# NEW_PDB.net
KiCad netlist of a schematic drawn in Altium Designer
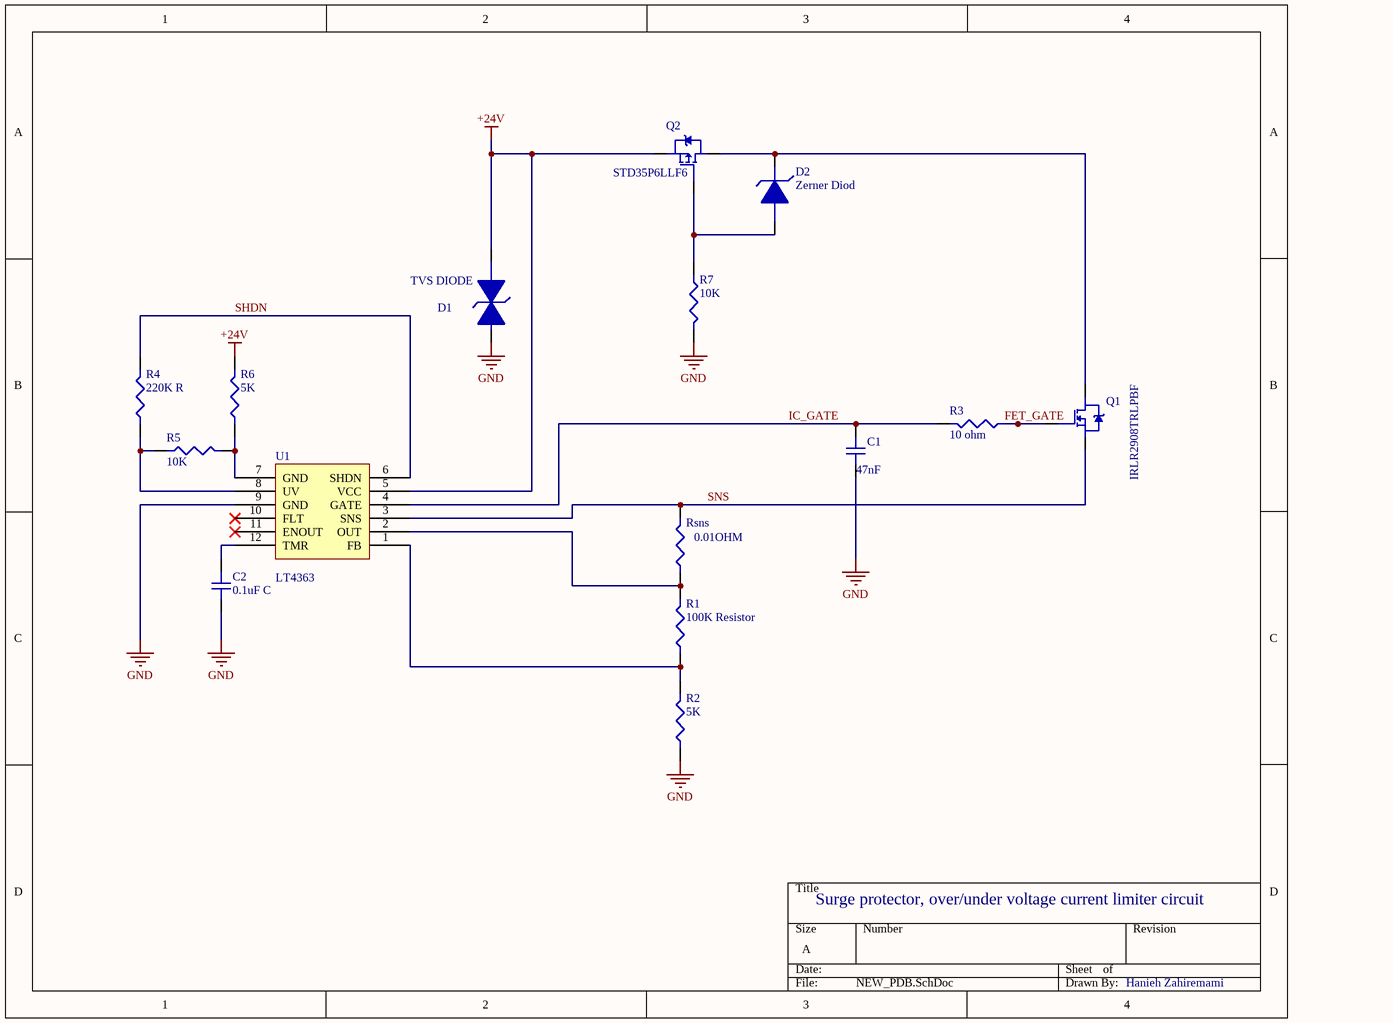
[diagram p0: NEW_PDB.SchDoc]

(export (version "E")
  (design (tool "Eeschema 10.0.6"))
  (components
    (comp (ref "C1")
      (value "47nF")
      (footprint "CAPC1613X09N")
      (description "CAP CER 0.047UF 50V X7R 0603")
      (fields
        (field (name "MANUFACTURER") "Murata")
        (field (name "MANUFACTURER PART NUMBER") "GCM188R71H473KA55D")
      )
      (libsource (lib "symbols") (part "GCM188R71H473KA55D"))
    )
    (comp (ref "C2")
      (value "0.1uF C")
      (footprint "CAPC1613X09N")
      (description "Cap Ceramic 0.1uF 25V X5R 10% SMD 0402 85C Paper T/R")
      (fields
        (field (name "MANUFACTURER") "Samsung")
        (field (name "MANUFACTURER PART NUMBER") "CL05A104KA5NNNC")
      )
      (libsource (lib "symbols") (part "CL05A104KA5NNNC"))
    )
    (comp (ref "D1")
      (value "TVS DIODE")
      (footprint "DIODE_TVS")
      (description "TVS DIODE 58VWM 93.6VC SMA")
      (fields (field (name "MANUFACTURER") "Diodes") (field (name "MANUFACTURER PART NUMBER") "SMAJ58A-13-F"))
      (libsource (lib "symbols") (part "SMAJ58A-13-F"))
    )
    (comp (ref "D2")
      (value "Zerner Diod")
      (footprint "DIOM3716X14N")
      (description "DIODE GEN PURP 100V 150MA SOD123")
      (fields (field (name "MANUFACTURER") "MCC") (field (name "MANUFACTURER PART NUMBER") "1N4148W-TP"))
      (libsource (lib "symbols") (part "1N4148W-TP"))
    )
    (comp (ref "Q1")
      (value "IRLR2908TRLPBF")
      (footprint "DPAK")
      (description "MOSFET N-CH 80V 30A DPAK")
      (fields (field (name "MANUFACTURER") "International Rectifier"))
      (libsource (lib "symbols") (part "IRLR2908TRLPBF"))
    )
    (comp (ref "Q2")
      (value "STD35P6LLF6")
      (footprint "DPAK")
      (description "POWER MOSFET")
      (fields (field (name "MANUFACTURER") "STMicroelectronics"))
      (libsource (lib "symbols") (part "STD35P6LLF6"))
    )
    (comp (ref "R1")
      (value "100K Resistor")
      (footprint "R0805")
      (description "Res Thin Film 0805 100K Ohm 0.1% 0.125W(1/8W) ±25ppm/C Molded SMD Automotive Punched T/R")
      (fields
        (field (name "MANUFACTURER") "Panasonic")
        (field (name "MANUFACTURER PART NUMBER") "ERA-6AEB104V")
      )
      (libsource (lib "symbols") (part "ERA-6AEB104V"))
    )
    (comp (ref "R2")
      (value "5K")
      (footprint "R0805")
      (description "Thin Film Resistors - SMD 200mW 5Kohm 0.1% 25ppm")
      (fields
        (field (name "MANUFACTURER") "Vishay Dale Thin Film")
        (field (name "MANUFACTURER PART NUMBER") "PNM0805E5001BST5")
      )
      (libsource (lib "symbols") (part "PNM0805E5001BST5"))
    )
    (comp (ref "R3")
      (value "10 ohm")
      (footprint "R0805")
      (description "RES SMD 10 OHM 1% 1/3W 0805")
      (fields
        (field (name "MANUFACTURER") "Susumu")
        (field (name "MANUFACTURER PART NUMBER") "RL1220S-100-F")
      )
      (libsource (lib "symbols") (part "RL1220S-100-F"))
    )
    (comp (ref "R4")
      (value "220K R")
      (footprint "R0805")
      (description "RES 220K OHM 1/8W 1% 0805 SMD")
      (fields (field (name "MANUFACTURER") "Rohm") (field (name "MANUFACTURER PART NUMBER") "KTR10EZPF2203"))
      (libsource (lib "symbols") (part "KTR10EZPF2203"))
    )
    (comp (ref "R5")
      (value "10K")
      (footprint "R0805")
      (description "Res Thin Film 0805 10K Ohm 0.5% 0.1W(1/10W) ±25ppm/C Molded SMD Paper T/R")
      (fields
        (field (name "MANUFACTURER") "Stackpole Electronics")
        (field (name "MANUFACTURER PART NUMBER") "RNCF0805DTE10K0")
      )
      (libsource (lib "symbols") (part "RNCF0805DTE10K0"))
    )
    (comp (ref "R6")
      (value "5K")
      (footprint "R0805")
      (description "Thin Film Resistors - SMD 200mW 5Kohm 0.1% 25ppm")
      (fields
        (field (name "MANUFACTURER") "Vishay Dale Thin Film")
        (field (name "MANUFACTURER PART NUMBER") "PNM0805E5001BST5")
      )
      (libsource (lib "symbols") (part "PNM0805E5001BST5"))
    )
    (comp (ref "R7")
      (value "10K")
      (footprint "R0805")
      (description "Res Thin Film 0805 10K Ohm 0.5% 0.1W(1/10W) ±25ppm/C Molded SMD Paper T/R")
      (fields
        (field (name "MANUFACTURER") "Stackpole Electronics")
        (field (name "MANUFACTURER PART NUMBER") "RNCF0805DTE10K0")
      )
      (libsource (lib "symbols") (part "RNCF0805DTE10K0"))
    )
    (comp (ref "Rsns")
      (value "0.01OHM")
      (footprint "R2512")
      (description "RES SMD 0.01 OHM 1% 2W 2512")
      (fields
        (field (name "MANUFACTURER") "Yageo")
        (field (name "MANUFACTURER PART NUMBER") "PE2512FKE7W0R01L")
      )
      (libsource (lib "symbols") (part "PE2512FKE7W0R01L"))
    )
    (comp (ref "U1")
      (value "LT4363")
      (footprint "TSOP65P490X110-12N")
      (description "IC SURGE STOPPER HV 12-MSOP")
      (fields
        (field (name "MANUFACTURER") "Analog Devices / Linear Technology")
        (field (name "MANUFACTURER PART NUMBER") "LT4363CMS-2#PBF")
      )
      (libsource (lib "symbols") (part "LT4363CMS-2#PBF"))
    )
  )
  (nets
    (net (code "1") (name "+24V") (class "Default")
      (node (ref "D1") (pin "2") (pinfunction "2_2") (pintype "passive"))
      (node (ref "Q2") (pin "4") (pinfunction "4_4") (pintype "passive"))
      (node (ref "R6") (pin "2") (pinfunction "2_2") (pintype "passive"))
      (node (ref "U1") (pin "5") (pinfunction "VCC_5") (pintype "passive"))
    )
    (net (code "2") (name "/FET_GATE") (class "Default")
      (node (ref "Q1") (pin "1") (pinfunction "1_1") (pintype "passive"))
      (node (ref "R3") (pin "1") (pinfunction "1_1") (pintype "passive"))
    )
    (net (code "3") (name "/IC_GATE") (class "Default")
      (node (ref "C1") (pin "2") (pinfunction "2_2") (pintype "passive"))
      (node (ref "R3") (pin "2") (pinfunction "2_2") (pintype "passive"))
      (node (ref "U1") (pin "4") (pinfunction "GATE_4") (pintype "passive"))
    )
    (net (code "4") (name "/SHDN") (class "Default")
      (node (ref "R4") (pin "2") (pinfunction "2_2") (pintype "passive"))
      (node (ref "U1") (pin "6") (pinfunction "SHDN_6") (pintype "passive"))
    )
    (net (code "5") (name "/SNS") (class "Default")
      (node (ref "Q1") (pin "3") (pinfunction "3_3") (pintype "passive"))
      (node (ref "Rsns") (pin "2") (pinfunction "2_2") (pintype "passive"))
      (node (ref "U1") (pin "3") (pinfunction "SNS_3") (pintype "passive"))
    )
    (net (code "6") (name "GND") (class "Default")
      (node (ref "C1") (pin "1") (pinfunction "1_1") (pintype "passive"))
      (node (ref "C2") (pin "1") (pinfunction "1_1") (pintype "passive"))
      (node (ref "D1") (pin "1") (pinfunction "1_1") (pintype "passive"))
      (node (ref "R2") (pin "1") (pinfunction "1_1") (pintype "passive"))
      (node (ref "R7") (pin "2") (pinfunction "2_2") (pintype "passive"))
      (node (ref "U1") (pin "9") (pinfunction "GND_9") (pintype "passive"))
    )
    (net (code "7") (name "Net-(D2-Pad1)") (class "Default")
      (node (ref "D2") (pin "1") (pinfunction "1_1") (pintype "passive"))
      (node (ref "Q1") (pin "4") (pinfunction "4_4") (pintype "passive"))
      (node (ref "Q2") (pin "3") (pinfunction "3_3") (pintype "passive"))
    )
    (net (code "8") (name "Net-(D2-Pad2)") (class "Default")
      (node (ref "D2") (pin "2") (pinfunction "2_2") (pintype "passive"))
      (node (ref "Q2") (pin "1") (pinfunction "1_1") (pintype "passive"))
      (node (ref "R7") (pin "1") (pinfunction "1_1") (pintype "passive"))
    )
    (net (code "9") (name "Net-(R5-Pad2)") (class "Default")
      (node (ref "R5") (pin "2") (pinfunction "2_2") (pintype "passive"))
      (node (ref "R6") (pin "1") (pinfunction "1_1") (pintype "passive"))
      (node (ref "U1") (pin "7") (pinfunction "GND_7") (pintype "passive"))
    )
    (net (code "10") (name "Net-(U1-FB)") (class "Default")
      (node (ref "R1") (pin "1") (pinfunction "1_1") (pintype "passive"))
      (node (ref "R2") (pin "2") (pinfunction "2_2") (pintype "passive"))
      (node (ref "U1") (pin "1") (pinfunction "FB_1") (pintype "passive"))
    )
    (net (code "11") (name "Net-(U1-OUT)") (class "Default")
      (node (ref "R1") (pin "2") (pinfunction "2_2") (pintype "passive"))
      (node (ref "Rsns") (pin "1") (pinfunction "1_1") (pintype "passive"))
      (node (ref "U1") (pin "2") (pinfunction "OUT_2") (pintype "passive"))
    )
    (net (code "12") (name "Net-(U1-TMR)") (class "Default")
      (node (ref "C2") (pin "2") (pinfunction "2_2") (pintype "passive"))
      (node (ref "U1") (pin "12") (pinfunction "TMR_12") (pintype "passive"))
    )
    (net (code "13") (name "Net-(U1-UV)") (class "Default")
      (node (ref "R4") (pin "1") (pinfunction "1_1") (pintype "passive"))
      (node (ref "R5") (pin "1") (pinfunction "1_1") (pintype "passive"))
      (node (ref "U1") (pin "8") (pinfunction "UV_8") (pintype "passive"))
    )
    (net (code "14") (name "unconnected-(U1-ENOUT-Pad11)") (class "Default")
      (node (ref "U1") (pin "11") (pinfunction "ENOUT_11") (pintype "passive+no_connect"))
    )
    (net (code "15") (name "unconnected-(U1-FLT-Pad10)") (class "Default")
      (node (ref "U1") (pin "10") (pinfunction "FLT_10") (pintype "passive+no_connect"))
    )
  )
)
